# Rev1_0.net
KiCad netlist of a schematic drawn in EAGLE
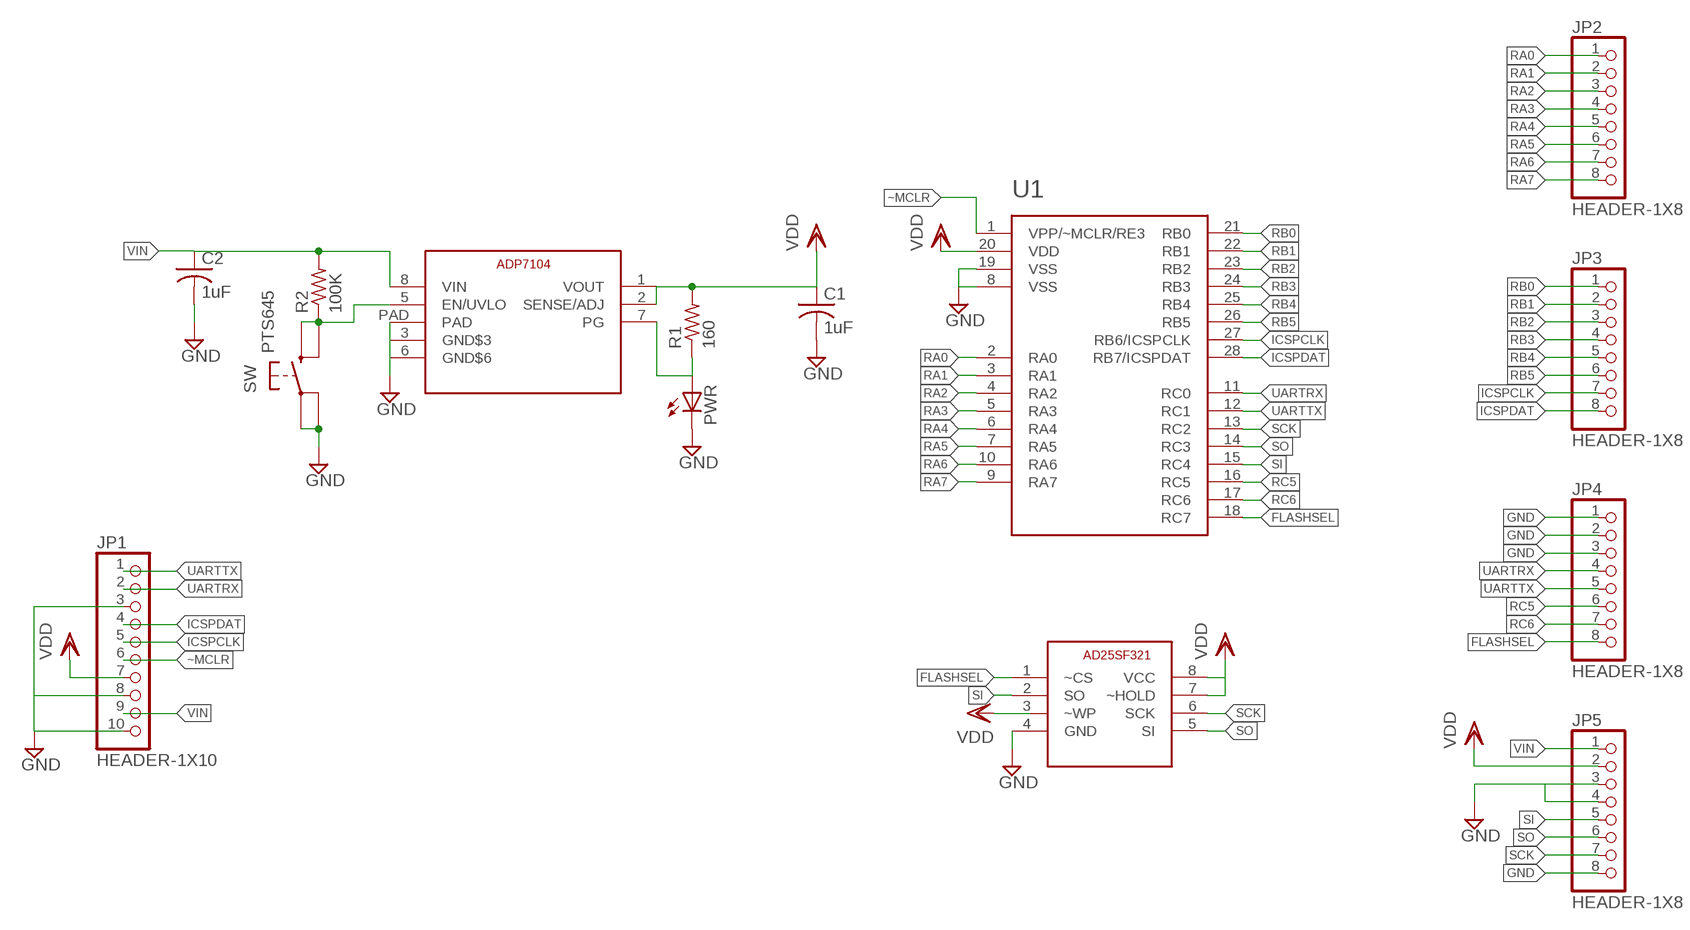
[diagram p0: schematic, sheet 1]

(export (version "E")
  (design (tool "Eeschema 10.0.6"))
  (components
    (comp (ref "C1")
      (value "1uF")
      (footprint "eagle-import:C0805")
      (libsource (lib "eagle-import") (part "C-USC0805"))
    )
    (comp (ref "C2")
      (value "1uF")
      (footprint "eagle-import:C0805")
      (libsource (lib "eagle-import") (part "C-USC0805"))
    )
    (comp (ref "JP1")
      (value "HEADER-1X10")
      (footprint "eagle-import:1X10")
      (libsource (lib "eagle-import") (part "HEADER-1X10"))
    )
    (comp (ref "JP2")
      (value "HEADER-1X8")
      (footprint "eagle-import:1X08")
      (libsource (lib "eagle-import") (part "HEADER-1X8"))
    )
    (comp (ref "JP3")
      (value "HEADER-1X8")
      (footprint "eagle-import:1X08")
      (libsource (lib "eagle-import") (part "HEADER-1X8"))
    )
    (comp (ref "JP4")
      (value "HEADER-1X8")
      (footprint "eagle-import:1X08")
      (libsource (lib "eagle-import") (part "HEADER-1X8"))
    )
    (comp (ref "JP5")
      (value "HEADER-1X8")
      (footprint "eagle-import:1X08")
      (libsource (lib "eagle-import") (part "HEADER-1X8"))
    )
    (comp (ref "PWR")
      (value "LEDCHIP-LED0805")
      (footprint "eagle-import:CHIP-LED0805")
      (libsource (lib "eagle-import") (part "LEDCHIP-LED0805"))
    )
    (comp (ref "R1")
      (value "160")
      (footprint "eagle-import:R0805")
      (libsource (lib "eagle-import") (part "R-US_R0805"))
    )
    (comp (ref "R2")
      (value "100K")
      (footprint "eagle-import:R0805")
      (libsource (lib "eagle-import") (part "R-US_R0805"))
    )
    (comp (ref "SW")
      (value "PTS645")
      (footprint "eagle-import:TSWITCH-6MM")
      (libsource (lib "eagle-import") (part "PTS645"))
    )
    (comp (ref "U1")
      (value "PIC16F1778")
      (footprint "eagle-import:SO28W")
      (libsource (lib "eagle-import") (part "PIC16F1778"))
    )
    (comp (ref "U2")
      (value "AT25SF321")
      (footprint "eagle-import:SOIC8")
      (libsource (lib "eagle-import") (part "AT25SF321"))
    )
    (comp (ref "U3")
      (value "ADP7104")
      (footprint "eagle-import:SOIC8-EXP-PAD")
      (libsource (lib "eagle-import") (part "ADP7104"))
    )
  )
  (nets
    (net (code "1") (name "/~{MCLR}") (class "Default")
      (node (ref "JP1") (pin "6") (pinfunction "6_6") (pintype "passive"))
      (node (ref "U1") (pin "1") (pinfunction "VPP/~{MCLR/RE3}_1") (pintype "bidirectional"))
    )
    (net (code "2") (name "FLASHSEL") (class "Default")
      (node (ref "JP4") (pin "8") (pinfunction "8_8") (pintype "passive"))
      (node (ref "U1") (pin "18") (pinfunction "RC7_18") (pintype "bidirectional"))
      (node (ref "U2") (pin "1") (pinfunction "~{CS}_1") (pintype "bidirectional"))
    )
    (net (code "3") (name "GND") (class "Default")
      (node (ref "C1") (pin "2") (pinfunction "2_2") (pintype "passive"))
      (node (ref "C2") (pin "2") (pinfunction "2_2") (pintype "passive"))
      (node (ref "JP1") (pin "10") (pinfunction "10_10") (pintype "passive"))
      (node (ref "JP1") (pin "3") (pinfunction "3_3") (pintype "passive"))
      (node (ref "JP1") (pin "8") (pinfunction "8_8") (pintype "passive"))
      (node (ref "JP4") (pin "1") (pinfunction "1_1") (pintype "passive"))
      (node (ref "JP4") (pin "2") (pinfunction "2_2") (pintype "passive"))
      (node (ref "JP4") (pin "3") (pinfunction "3_3") (pintype "passive"))
      (node (ref "JP5") (pin "3") (pinfunction "3_3") (pintype "passive"))
      (node (ref "JP5") (pin "4") (pinfunction "4_4") (pintype "passive"))
      (node (ref "JP5") (pin "8") (pinfunction "8_8") (pintype "passive"))
      (node (ref "PWR") (pin "C") (pinfunction "C_C") (pintype "passive"))
      (node (ref "SW") (pin "P$1") (pinfunction "P$1_P$1") (pintype "bidirectional"))
      (node (ref "SW") (pin "P$2") (pinfunction "P$2_P$2") (pintype "bidirectional"))
      (node (ref "U1") (pin "19") (pinfunction "VSS_19") (pintype "bidirectional"))
      (node (ref "U1") (pin "8") (pinfunction "VSS_8") (pintype "bidirectional"))
      (node (ref "U2") (pin "4") (pinfunction "GND_4") (pintype "bidirectional"))
      (node (ref "U3") (pin "PAD") (pinfunction "PAD_PAD") (pintype "bidirectional"))
    )
    (net (code "4") (name "ICSPCLK") (class "Default")
      (node (ref "JP1") (pin "5") (pinfunction "5_5") (pintype "passive"))
      (node (ref "JP3") (pin "7") (pinfunction "7_7") (pintype "passive"))
      (node (ref "U1") (pin "27") (pinfunction "RB6/ICSPCLK_27") (pintype "bidirectional"))
    )
    (net (code "5") (name "ICSPDAT") (class "Default")
      (node (ref "JP1") (pin "4") (pinfunction "4_4") (pintype "passive"))
      (node (ref "JP3") (pin "8") (pinfunction "8_8") (pintype "passive"))
      (node (ref "U1") (pin "28") (pinfunction "RB7/ICSPDAT_28") (pintype "bidirectional"))
    )
    (net (code "6") (name "Net-(U3-EN{slash}UVLO)") (class "Default")
      (node (ref "R2") (pin "1") (pinfunction "1_1") (pintype "passive"))
      (node (ref "SW") (pin "P$3") (pinfunction "P$3_P$3") (pintype "bidirectional"))
      (node (ref "SW") (pin "P$4") (pinfunction "P$4_P$4") (pintype "bidirectional"))
      (node (ref "U3") (pin "5") (pinfunction "EN/UVLO_5") (pintype "bidirectional"))
    )
    (net (code "7") (name "Net-(U3-PG)") (class "Default")
      (node (ref "PWR") (pin "A") (pinfunction "A_A") (pintype "passive"))
      (node (ref "R1") (pin "1") (pinfunction "1_1") (pintype "passive"))
      (node (ref "U3") (pin "7") (pinfunction "PG_7") (pintype "bidirectional"))
    )
    (net (code "8") (name "RA0") (class "Default")
      (node (ref "JP2") (pin "1") (pinfunction "1_1") (pintype "passive"))
      (node (ref "U1") (pin "2") (pinfunction "RA0_2") (pintype "bidirectional"))
    )
    (net (code "9") (name "RA1") (class "Default")
      (node (ref "JP2") (pin "2") (pinfunction "2_2") (pintype "passive"))
      (node (ref "U1") (pin "3") (pinfunction "RA1_3") (pintype "bidirectional"))
    )
    (net (code "10") (name "RA2") (class "Default")
      (node (ref "JP2") (pin "3") (pinfunction "3_3") (pintype "passive"))
      (node (ref "U1") (pin "4") (pinfunction "RA2_4") (pintype "bidirectional"))
    )
    (net (code "11") (name "RA3") (class "Default")
      (node (ref "JP2") (pin "4") (pinfunction "4_4") (pintype "passive"))
      (node (ref "U1") (pin "5") (pinfunction "RA3_5") (pintype "bidirectional"))
    )
    (net (code "12") (name "RA4") (class "Default")
      (node (ref "JP2") (pin "5") (pinfunction "5_5") (pintype "passive"))
      (node (ref "U1") (pin "6") (pinfunction "RA4_6") (pintype "bidirectional"))
    )
    (net (code "13") (name "RA5") (class "Default")
      (node (ref "JP2") (pin "6") (pinfunction "6_6") (pintype "passive"))
      (node (ref "U1") (pin "7") (pinfunction "RA5_7") (pintype "bidirectional"))
    )
    (net (code "14") (name "RA6") (class "Default")
      (node (ref "JP2") (pin "7") (pinfunction "7_7") (pintype "passive"))
      (node (ref "U1") (pin "10") (pinfunction "RA6_10") (pintype "bidirectional"))
    )
    (net (code "15") (name "RA7") (class "Default")
      (node (ref "JP2") (pin "8") (pinfunction "8_8") (pintype "passive"))
      (node (ref "U1") (pin "9") (pinfunction "RA7_9") (pintype "bidirectional"))
    )
    (net (code "16") (name "RB0") (class "Default")
      (node (ref "JP3") (pin "1") (pinfunction "1_1") (pintype "passive"))
      (node (ref "U1") (pin "21") (pinfunction "RB0_21") (pintype "bidirectional"))
    )
    (net (code "17") (name "RB1") (class "Default")
      (node (ref "JP3") (pin "2") (pinfunction "2_2") (pintype "passive"))
      (node (ref "U1") (pin "22") (pinfunction "RB1_22") (pintype "bidirectional"))
    )
    (net (code "18") (name "RB2") (class "Default")
      (node (ref "JP3") (pin "3") (pinfunction "3_3") (pintype "passive"))
      (node (ref "U1") (pin "23") (pinfunction "RB2_23") (pintype "bidirectional"))
    )
    (net (code "19") (name "RB3") (class "Default")
      (node (ref "JP3") (pin "4") (pinfunction "4_4") (pintype "passive"))
      (node (ref "U1") (pin "24") (pinfunction "RB3_24") (pintype "bidirectional"))
    )
    (net (code "20") (name "RB4") (class "Default")
      (node (ref "JP3") (pin "5") (pinfunction "5_5") (pintype "passive"))
      (node (ref "U1") (pin "25") (pinfunction "RB4_25") (pintype "bidirectional"))
    )
    (net (code "21") (name "RB5") (class "Default")
      (node (ref "JP3") (pin "6") (pinfunction "6_6") (pintype "passive"))
      (node (ref "U1") (pin "26") (pinfunction "RB5_26") (pintype "bidirectional"))
    )
    (net (code "22") (name "RC5") (class "Default")
      (node (ref "JP4") (pin "6") (pinfunction "6_6") (pintype "passive"))
      (node (ref "U1") (pin "16") (pinfunction "RC5_16") (pintype "bidirectional"))
    )
    (net (code "23") (name "RC6") (class "Default")
      (node (ref "JP4") (pin "7") (pinfunction "7_7") (pintype "passive"))
      (node (ref "U1") (pin "17") (pinfunction "RC6_17") (pintype "bidirectional"))
    )
    (net (code "24") (name "SCK") (class "Default")
      (node (ref "JP5") (pin "7") (pinfunction "7_7") (pintype "passive"))
      (node (ref "U1") (pin "13") (pinfunction "RC2_13") (pintype "bidirectional"))
      (node (ref "U2") (pin "6") (pinfunction "SCK_6") (pintype "bidirectional"))
    )
    (net (code "25") (name "SI") (class "Default")
      (node (ref "JP5") (pin "5") (pinfunction "5_5") (pintype "passive"))
      (node (ref "U1") (pin "15") (pinfunction "RC4_15") (pintype "bidirectional"))
      (node (ref "U2") (pin "2") (pinfunction "SO_2") (pintype "bidirectional"))
    )
    (net (code "26") (name "SO") (class "Default")
      (node (ref "JP5") (pin "6") (pinfunction "6_6") (pintype "passive"))
      (node (ref "U1") (pin "14") (pinfunction "RC3_14") (pintype "bidirectional"))
      (node (ref "U2") (pin "5") (pinfunction "SI_5") (pintype "bidirectional"))
    )
    (net (code "27") (name "UARTRX") (class "Default")
      (node (ref "JP1") (pin "2") (pinfunction "2_2") (pintype "passive"))
      (node (ref "JP4") (pin "4") (pinfunction "4_4") (pintype "passive"))
      (node (ref "U1") (pin "11") (pinfunction "RC0_11") (pintype "bidirectional"))
    )
    (net (code "28") (name "UARTTX") (class "Default")
      (node (ref "JP1") (pin "1") (pinfunction "1_1") (pintype "passive"))
      (node (ref "JP4") (pin "5") (pinfunction "5_5") (pintype "passive"))
      (node (ref "U1") (pin "12") (pinfunction "RC1_12") (pintype "bidirectional"))
    )
    (net (code "29") (name "VDD") (class "Default")
      (node (ref "C1") (pin "1") (pinfunction "1_1") (pintype "passive"))
      (node (ref "JP1") (pin "7") (pinfunction "7_7") (pintype "passive"))
      (node (ref "JP5") (pin "2") (pinfunction "2_2") (pintype "passive"))
      (node (ref "R1") (pin "2") (pinfunction "2_2") (pintype "passive"))
      (node (ref "U1") (pin "20") (pinfunction "VDD_20") (pintype "bidirectional"))
      (node (ref "U2") (pin "7") (pinfunction "~{HOLD}_7") (pintype "bidirectional"))
      (node (ref "U2") (pin "8") (pinfunction "VCC_8") (pintype "bidirectional"))
      (node (ref "U3") (pin "1") (pinfunction "VOUT_1") (pintype "bidirectional"))
      (node (ref "U3") (pin "2") (pinfunction "SENSE/ADJ_2") (pintype "bidirectional"))
    )
    (net (code "30") (name "VIN") (class "Default")
      (node (ref "C2") (pin "1") (pinfunction "1_1") (pintype "passive"))
      (node (ref "JP1") (pin "9") (pinfunction "9_9") (pintype "passive"))
      (node (ref "JP5") (pin "1") (pinfunction "1_1") (pintype "passive"))
      (node (ref "R2") (pin "2") (pinfunction "2_2") (pintype "passive"))
      (node (ref "U3") (pin "8") (pinfunction "VIN_8") (pintype "bidirectional"))
    )
    (net (code "31") (name "unconnected-(U2-~{WP}-Pad3)") (class "Default")
      (node (ref "U2") (pin "3") (pinfunction "~{WP}_3") (pintype "bidirectional"))
    )
    (net (code "32") (name "unconnected-(U3-GND$3-Pad3)") (class "Default")
      (node (ref "U3") (pin "3") (pinfunction "GND$3_3") (pintype "bidirectional"))
    )
    (net (code "33") (name "unconnected-(U3-GND$6-Pad6)") (class "Default")
      (node (ref "U3") (pin "6") (pinfunction "GND$6_6") (pintype "bidirectional"))
    )
  )
)
